# Sheet_D1.net
KiCad netlist of a schematic drawn in Altium Designer
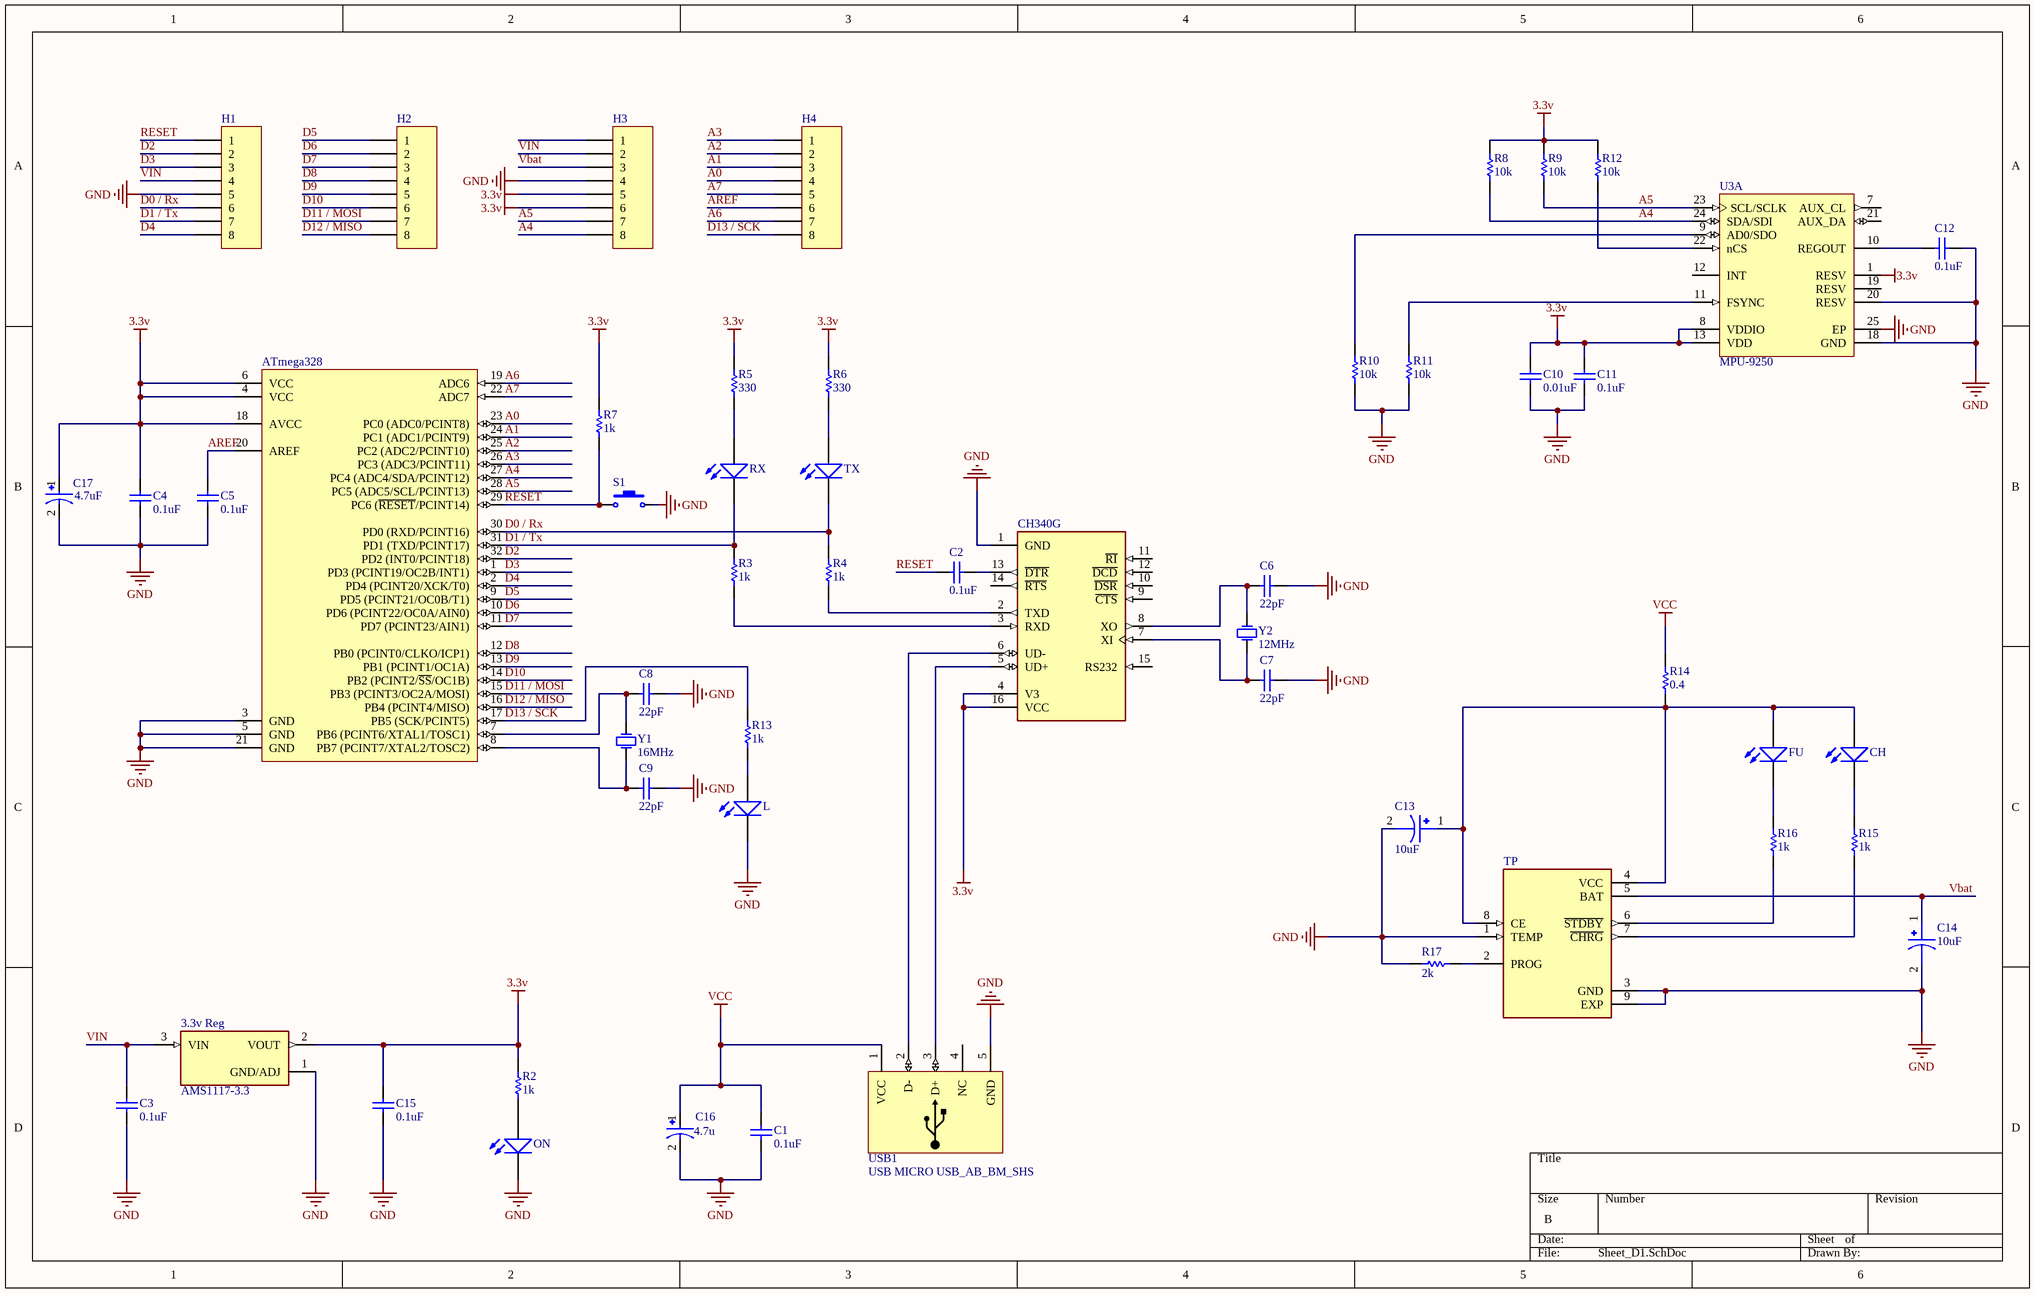
[diagram p0: Sheet_D1.SchDoc]

(export (version "E")
  (design (tool "Eeschema 10.0.6"))
  (components
    (comp (ref "3.3v Reg")
      (value "AMS1117-3.3")
      (footprint "SOT229P700X180-4N")
      (description "Sot223/Pkg 1-Amp 3.3-Volt Low Drop Out Voltage Regulatator")
      (fields (field (name "MF") "Advanced Monolithic Systems"))
      (libsource (lib "AMS1117-3.3") (part "AMS1117-3.3"))
    )
    (comp (ref "ATmega328")
      (value "~")
      (footprint "32A_L")
      (libsource (lib "Altium Content Vault") (part "MC-8B-ATM48-SQ32"))
    )
    (comp (ref "C1")
      (value "0.1uF")
      (footprint "CAP0805")
      (description "CAP0805")
      (libsource (lib "CAP0805") (part "CAP0805"))
    )
    (comp (ref "C2")
      (value "0.1uF")
      (footprint "CAP0805")
      (description "CAP0805")
      (libsource (lib "CAP0805") (part "CAP0805"))
    )
    (comp (ref "C3")
      (value "0.1uF")
      (footprint "CAP0805")
      (description "CAP0805")
      (libsource (lib "CAP0805") (part "CAP0805"))
    )
    (comp (ref "C4")
      (value "0.1uF")
      (footprint "CAP0805")
      (description "CAP0805")
      (libsource (lib "CAP0805") (part "CAP0805"))
    )
    (comp (ref "C5")
      (value "0.1uF")
      (footprint "CAP0805")
      (description "CAP0805")
      (libsource (lib "CAP0805") (part "CAP0805"))
    )
    (comp (ref "C6")
      (value "22pF")
      (footprint "CAP0805")
      (description "CAP0805")
      (libsource (lib "CAP0805") (part "CAP0805"))
    )
    (comp (ref "C7")
      (value "22pF")
      (footprint "CAP0805")
      (description "CAP0805")
      (libsource (lib "CAP0805") (part "CAP0805"))
    )
    (comp (ref "C8")
      (value "22pF")
      (footprint "CAP0805")
      (description "CAP0805")
      (libsource (lib "CAP0805") (part "CAP0805"))
    )
    (comp (ref "C9")
      (value "22pF")
      (footprint "CAP0805")
      (description "CAP0805")
      (libsource (lib "CAP0805") (part "CAP0805"))
    )
    (comp (ref "C10")
      (value "0.01uF")
      (footprint "CAP0805")
      (description "CAP0805")
      (libsource (lib "CAP0805") (part "CAP0805"))
    )
    (comp (ref "C11")
      (value "0.1uF")
      (footprint "CAP0805")
      (description "CAP0805")
      (libsource (lib "CAP0805") (part "CAP0805"))
    )
    (comp (ref "C12")
      (value "0.1uF")
      (footprint "CAP0805")
      (description "CAP0805")
      (libsource (lib "CAP0805") (part "CAP0805"))
    )
    (comp (ref "C13")
      (value "10uF")
      (footprint "CAPMP3216X180N")
      (fields (field (name "MP") "TAJA106K016RNJ") (field (name "MF") "AVX"))
      (libsource (lib "") (part "TAJA106K016RNJ_1"))
    )
    (comp (ref "C14")
      (value "10uF")
      (footprint "CAPMP3216X180N")
      (fields (field (name "MP") "TAJA106K016RNJ") (field (name "MF") "AVX"))
      (libsource (lib "TAJA106K016RNJ") (part "TAJA106K016RNJ"))
    )
    (comp (ref "C15")
      (value "0.1uF")
      (footprint "CAP0805")
      (description "CAP0805")
      (libsource (lib "CAP0805") (part "CAP0805"))
    )
    (comp (ref "C16")
      (value "4.7u")
      (footprint "CAPMP3516X190N")
      (description "4.7 ÂµF Molded Tantalum Capacitors 25 V 1411 (3528 Metric), 1210 1.5Ohm")
      (fields (field (name "MP") "TAJB475K025RNJ") (field (name "MF") "AVX"))
      (libsource (lib "TAJB475K025RNJ") (part "TAJB475K025RNJ"))
    )
    (comp (ref "C17")
      (value "4.7uF")
      (footprint "CAPMP3516X190N")
      (description "4.7 ÂµF Molded Tantalum Capacitors 25 V 1411 (3528 Metric), 1210 1.5Ohm")
      (fields (field (name "MP") "TAJB475K025RNJ") (field (name "MF") "AVX"))
      (libsource (lib "TAJB475K025RNJ") (part "TAJB475K025RNJ"))
    )
    (comp (ref "CH")
      (value "~")
      (footprint "LED_SMD_0805")
      (libsource (lib "LED_SMD_0805") (part "LED_SMD_0805"))
    )
    (comp (ref "CH340G")
      (value "~")
      (footprint "SOIC127P600X180-16N")
      (description "USB Interface Integrated Circuit")
      (fields (field (name "MP") "Ch340G") (field (name "MF") "WCH"))
      (libsource (lib "CH340G") (part "CH340G"))
    )
    (comp (ref "FU")
      (value "~")
      (footprint "LED_SMD_0805")
      (libsource (lib "LED_SMD_0805") (part "LED_SMD_0805"))
    )
    (comp (ref "H1") (value "~") (footprint "Header 8") (libsource (lib "Header 8") (part "Header 8")))
    (comp (ref "H2") (value "~") (footprint "Header 8") (libsource (lib "Header 8") (part "Header 8")))
    (comp (ref "H3") (value "~") (footprint "Header 8") (libsource (lib "Header 8") (part "Header 8")))
    (comp (ref "H4") (value "~") (footprint "Header 8") (libsource (lib "Header 8") (part "Header 8")))
    (comp (ref "L")
      (value "~")
      (footprint "LED_SMD_0805")
      (libsource (lib "LED_SMD_0805") (part "LED_SMD_0805"))
    )
    (comp (ref "ON")
      (value "~")
      (footprint "LED_SMD_0805")
      (libsource (lib "LED_SMD_0805") (part "LED_SMD_0805"))
    )
    (comp (ref "R2")
      (value "1k")
      (footprint "RES0805")
      (description "RES0805")
      (libsource (lib "RES0805") (part "RES0805"))
    )
    (comp (ref "R3")
      (value "1k")
      (footprint "RES0805")
      (description "RES0805")
      (libsource (lib "RES0805") (part "RES0805"))
    )
    (comp (ref "R4")
      (value "1k")
      (footprint "RES0805")
      (description "RES0805")
      (libsource (lib "RES0805") (part "RES0805"))
    )
    (comp (ref "R5")
      (value "330")
      (footprint "RES0805")
      (description "RES0805")
      (libsource (lib "RES0805") (part "RES0805"))
    )
    (comp (ref "R6")
      (value "330")
      (footprint "RES0805")
      (description "RES0805")
      (libsource (lib "RES0805") (part "RES0805"))
    )
    (comp (ref "R7")
      (value "1k")
      (footprint "RES0805")
      (description "RES0805")
      (libsource (lib "RES0805") (part "RES0805"))
    )
    (comp (ref "R8")
      (value "10k")
      (footprint "RES0805")
      (description "RES0805")
      (libsource (lib "RES0805") (part "RES0805"))
    )
    (comp (ref "R9")
      (value "10k")
      (footprint "RES0805")
      (description "RES0805")
      (libsource (lib "RES0805") (part "RES0805"))
    )
    (comp (ref "R10")
      (value "10k")
      (footprint "RES0805")
      (description "RES0805")
      (libsource (lib "RES0805") (part "RES0805"))
    )
    (comp (ref "R11")
      (value "10k")
      (footprint "RES0805")
      (description "RES0805")
      (libsource (lib "RES0805") (part "RES0805"))
    )
    (comp (ref "R12")
      (value "10k")
      (footprint "RES0805")
      (description "RES0805")
      (libsource (lib "RES0805") (part "RES0805"))
    )
    (comp (ref "R13")
      (value "1k")
      (footprint "RES0805")
      (description "RES0805")
      (libsource (lib "RES0805") (part "RES0805"))
    )
    (comp (ref "R14")
      (value "0.4")
      (footprint "RES0805")
      (description "RES0805")
      (libsource (lib "RES0805") (part "RES0805"))
    )
    (comp (ref "R15")
      (value "1k")
      (footprint "RES0805")
      (description "RES0805")
      (libsource (lib "RES0805") (part "RES0805"))
    )
    (comp (ref "R16")
      (value "1k")
      (footprint "RES0805")
      (description "RES0805")
      (libsource (lib "RES0805") (part "RES0805"))
    )
    (comp (ref "R17")
      (value "2k")
      (footprint "RES0805")
      (description "RES0805")
      (libsource (lib "RES0805") (part "RES0805"))
    )
    (comp (ref "RX")
      (value "~")
      (footprint "LED_SMD_0805")
      (libsource (lib "LED_SMD_0805") (part "LED_SMD_0805"))
    )
    (comp (ref "S1")
      (value "~")
      (footprint "Push Button Switch SMD")
      (libsource (lib "Push Button Switch SMD") (part "Push Button Switch SMD"))
    )
    (comp (ref "TP")
      (value "~")
      (footprint "SOIC127P600X175-9N")
      (description "TP4056-42-ESOP8 TP")
      (fields (field (name "MF") "Lite-On Semiconductor") (field (name "MP") "TP4056-42-ESOP8"))
      (libsource (lib "TP4056-42-ESOP8") (part "TP4056-42-ESOP8"))
    )
    (comp (ref "TX")
      (value "~")
      (footprint "LED_SMD_0805")
      (libsource (lib "LED_SMD_0805") (part "LED_SMD_0805"))
    )
    (comp (ref "U3")
      (value "MPU-9250")
      (footprint "INSE-QFN-24-1700X1540TP_M")
      (description "9-axis MotionTracking device, 2.4 to 3,6 V, -40 to 85 degC, 24-Pin QFN, RoHS, Tape and Reel")
      (fields (field (name "MANUFACTURER") "InvenSense"))
      (libsource (lib "Altium Content Vault") (part "INSE-MPU-9250-QFN-24"))
    )
    (comp (ref "USB1")
      (value "USB MICRO USB_AB_BM_SHS")
      (footprint "USB MICRO USB_AB_BM_SHS")
      (libsource (lib "USB MICRO USB_AB_BM_SHS") (part "USB MICRO USB_AB_BM_SHS"))
    )
    (comp (ref "Y1")
      (value "16MHz")
      (footprint "Crystal SMD")
      (description "Crystal SMD")
      (libsource (lib "Crystal SMD") (part "Crystal SMD"))
    )
    (comp (ref "Y2")
      (value "12MHz")
      (footprint "Crystal SMD")
      (description "Crystal SMD")
      (libsource (lib "Crystal SMD") (part "Crystal SMD"))
    )
  )
  (nets
    (net (code "1") (name "/A0") (class "Default")
      (node (ref "ATmega328") (pin "23") (pinfunction "PC0_(ADC0/PCINT8)_23") (pintype "bidirectional"))
      (node (ref "H4") (pin "4") (pinfunction "4_4") (pintype "passive"))
    )
    (net (code "2") (name "/A1") (class "Default")
      (node (ref "ATmega328") (pin "24") (pinfunction "PC1_(ADC1/PCINT9)_24") (pintype "bidirectional"))
      (node (ref "H4") (pin "3") (pinfunction "3_3") (pintype "passive"))
    )
    (net (code "3") (name "/A2") (class "Default")
      (node (ref "ATmega328") (pin "25") (pinfunction "PC2_(ADC2/PCINT10)_25") (pintype "bidirectional"))
      (node (ref "H4") (pin "2") (pinfunction "2_2") (pintype "passive"))
    )
    (net (code "4") (name "/A3") (class "Default")
      (node (ref "ATmega328") (pin "26") (pinfunction "PC3_(ADC3/PCINT11)_26") (pintype "bidirectional"))
      (node (ref "H4") (pin "1") (pinfunction "1_1") (pintype "passive"))
    )
    (net (code "5") (name "/A4") (class "Default")
      (node (ref "ATmega328") (pin "27") (pinfunction "PC4_(ADC4/SDA/PCINT12)_27") (pintype "bidirectional"))
      (node (ref "H3") (pin "8") (pinfunction "8_8") (pintype "passive"))
      (node (ref "R8") (pin "1") (pinfunction "1_1") (pintype "passive"))
      (node (ref "U3") (pin "24") (pinfunction "SDA/SDI_24") (pintype "bidirectional"))
    )
    (net (code "6") (name "/A5") (class "Default")
      (node (ref "ATmega328") (pin "28") (pinfunction "PC5_(ADC5/SCL/PCINT13)_28") (pintype "bidirectional"))
      (node (ref "H3") (pin "7") (pinfunction "7_7") (pintype "passive"))
      (node (ref "R9") (pin "1") (pinfunction "1_1") (pintype "passive"))
      (node (ref "U3") (pin "23") (pinfunction "SCL/SCLK_23") (pintype "input"))
    )
    (net (code "7") (name "/A6") (class "Default")
      (node (ref "ATmega328") (pin "19") (pinfunction "ADC6_19") (pintype "input"))
      (node (ref "H4") (pin "7") (pinfunction "7_7") (pintype "passive"))
    )
    (net (code "8") (name "/A7") (class "Default")
      (node (ref "ATmega328") (pin "22") (pinfunction "ADC7_22") (pintype "input"))
      (node (ref "H4") (pin "5") (pinfunction "5_5") (pintype "passive"))
    )
    (net (code "9") (name "/AREF") (class "Default")
      (node (ref "ATmega328") (pin "20") (pinfunction "AREF_20") (pintype "passive"))
      (node (ref "C5") (pin "2") (pinfunction "2_2") (pintype "passive"))
      (node (ref "H4") (pin "6") (pinfunction "6_6") (pintype "passive"))
    )
    (net (code "10") (name "/D0 {slash} Rx") (class "Default")
      (node (ref "ATmega328") (pin "30") (pinfunction "PD0_(RXD/PCINT16)_30") (pintype "bidirectional"))
      (node (ref "H1") (pin "6") (pinfunction "6_6") (pintype "passive"))
      (node (ref "R4") (pin "2") (pinfunction "2_2") (pintype "passive"))
      (node (ref "TX") (pin "1") (pinfunction "K_1") (pintype "passive"))
    )
    (net (code "11") (name "/D1 {slash} Tx") (class "Default")
      (node (ref "ATmega328") (pin "31") (pinfunction "PD1_(TXD/PCINT17)_31") (pintype "bidirectional"))
      (node (ref "H1") (pin "7") (pinfunction "7_7") (pintype "passive"))
      (node (ref "R3") (pin "2") (pinfunction "2_2") (pintype "passive"))
      (node (ref "RX") (pin "1") (pinfunction "K_1") (pintype "passive"))
    )
    (net (code "12") (name "/D2") (class "Default")
      (node (ref "ATmega328") (pin "32") (pinfunction "PD2_(INT0/PCINT18)_32") (pintype "bidirectional"))
      (node (ref "H1") (pin "2") (pinfunction "2_2") (pintype "passive"))
    )
    (net (code "13") (name "/D3") (class "Default")
      (node (ref "ATmega328") (pin "1") (pinfunction "PD3_(PCINT19/OC2B/INT1)_1") (pintype "bidirectional"))
      (node (ref "H1") (pin "3") (pinfunction "3_3") (pintype "passive"))
    )
    (net (code "14") (name "/D4") (class "Default")
      (node (ref "ATmega328") (pin "2") (pinfunction "PD4_(PCINT20/XCK/T0)_2") (pintype "bidirectional"))
      (node (ref "H1") (pin "8") (pinfunction "8_8") (pintype "passive"))
    )
    (net (code "15") (name "/D5") (class "Default")
      (node (ref "ATmega328") (pin "9") (pinfunction "PD5_(PCINT21/OC0B/T1)_9") (pintype "bidirectional"))
      (node (ref "H2") (pin "1") (pinfunction "1_1") (pintype "passive"))
    )
    (net (code "16") (name "/D6") (class "Default")
      (node (ref "ATmega328") (pin "10") (pinfunction "PD6_(PCINT22/OC0A/AIN0)_10") (pintype "bidirectional"))
      (node (ref "H2") (pin "2") (pinfunction "2_2") (pintype "passive"))
    )
    (net (code "17") (name "/D7") (class "Default")
      (node (ref "ATmega328") (pin "11") (pinfunction "PD7_(PCINT23/AIN1)_11") (pintype "bidirectional"))
      (node (ref "H2") (pin "3") (pinfunction "3_3") (pintype "passive"))
    )
    (net (code "18") (name "/D8") (class "Default")
      (node (ref "ATmega328") (pin "12") (pinfunction "PB0_(PCINT0/CLKO/ICP1)_12") (pintype "bidirectional"))
      (node (ref "H2") (pin "4") (pinfunction "4_4") (pintype "passive"))
    )
    (net (code "19") (name "/D9") (class "Default")
      (node (ref "ATmega328") (pin "13") (pinfunction "PB1_(PCINT1/OC1A)_13") (pintype "bidirectional"))
      (node (ref "H2") (pin "5") (pinfunction "5_5") (pintype "passive"))
    )
    (net (code "20") (name "/D10") (class "Default")
      (node (ref "ATmega328") (pin "14") (pinfunction "PB2_(PCINT2/~{SS}/OC1B)_14") (pintype "bidirectional"))
      (node (ref "H2") (pin "6") (pinfunction "6_6") (pintype "passive"))
    )
    (net (code "21") (name "/D11 {slash} MOSI") (class "Default")
      (node (ref "ATmega328") (pin "15") (pinfunction "PB3_(PCINT3/OC2A/MOSI)_15") (pintype "bidirectional"))
      (node (ref "H2") (pin "7") (pinfunction "7_7") (pintype "passive"))
    )
    (net (code "22") (name "/D12 {slash} MISO") (class "Default")
      (node (ref "ATmega328") (pin "16") (pinfunction "PB4_(PCINT4/MISO)_16") (pintype "bidirectional"))
      (node (ref "H2") (pin "8") (pinfunction "8_8") (pintype "passive"))
    )
    (net (code "23") (name "/D13 {slash} SCK") (class "Default")
      (node (ref "ATmega328") (pin "17") (pinfunction "PB5_(SCK/PCINT5)_17") (pintype "bidirectional"))
      (node (ref "H4") (pin "8") (pinfunction "8_8") (pintype "passive"))
      (node (ref "R13") (pin "1") (pinfunction "1_1") (pintype "passive"))
    )
    (net (code "24") (name "/RESET") (class "Default")
      (node (ref "ATmega328") (pin "29") (pinfunction "PC6_(~{RESET}/PCINT14)_29") (pintype "bidirectional"))
      (node (ref "C2") (pin "2") (pinfunction "2_2") (pintype "passive"))
      (node (ref "H1") (pin "1") (pinfunction "1_1") (pintype "passive"))
      (node (ref "R7") (pin "1") (pinfunction "1_1") (pintype "passive"))
      (node (ref "S1") (pin "1") (pinfunction "1_1") (pintype "passive"))
    )
    (net (code "25") (name "/VIN") (class "Default")
      (node (ref "3.3v Reg") (pin "3") (pinfunction "VIN_3") (pintype "input"))
      (node (ref "C3") (pin "1") (pinfunction "1_1") (pintype "passive"))
      (node (ref "H1") (pin "4") (pinfunction "4_4") (pintype "passive"))
      (node (ref "H3") (pin "2") (pinfunction "2_2") (pintype "passive"))
    )
    (net (code "26") (name "/Vbat") (class "Default")
      (node (ref "C14") (pin "1") (pinfunction "1_1") (pintype "passive"))
      (node (ref "H3") (pin "3") (pinfunction "3_3") (pintype "passive"))
      (node (ref "TP") (pin "5") (pinfunction "BAT_5") (pintype "power_in"))
    )
    (net (code "27") (name "3.3v") (class "Default")
      (node (ref "3.3v Reg") (pin "2") (pinfunction "VOUT_2") (pintype "output"))
      (node (ref "ATmega328") (pin "18") (pinfunction "AVCC_18") (pintype "power_in"))
      (node (ref "ATmega328") (pin "4") (pinfunction "VCC_4") (pintype "power_in"))
      (node (ref "ATmega328") (pin "6") (pinfunction "VCC_6") (pintype "power_in"))
      (node (ref "C10") (pin "2") (pinfunction "2_2") (pintype "passive"))
      (node (ref "C11") (pin "2") (pinfunction "2_2") (pintype "passive"))
      (node (ref "C15") (pin "2") (pinfunction "2_2") (pintype "passive"))
      (node (ref "C17") (pin "1") (pinfunction "1_1") (pintype "passive"))
      (node (ref "C4") (pin "1") (pinfunction "1_1") (pintype "passive"))
      (node (ref "CH340G") (pin "16") (pinfunction "VCC_16") (pintype "power_in"))
      (node (ref "CH340G") (pin "4") (pinfunction "V3_4") (pintype "power_in"))
      (node (ref "H3") (pin "5") (pinfunction "5_5") (pintype "passive"))
      (node (ref "H3") (pin "6") (pinfunction "6_6") (pintype "passive"))
      (node (ref "R12") (pin "2") (pinfunction "2_2") (pintype "passive"))
      (node (ref "R2") (pin "2") (pinfunction "2_2") (pintype "passive"))
      (node (ref "R5") (pin "2") (pinfunction "2_2") (pintype "passive"))
      (node (ref "R6") (pin "2") (pinfunction "2_2") (pintype "passive"))
      (node (ref "R7") (pin "2") (pinfunction "2_2") (pintype "passive"))
      (node (ref "R8") (pin "2") (pinfunction "2_2") (pintype "passive"))
      (node (ref "R9") (pin "2") (pinfunction "2_2") (pintype "passive"))
      (node (ref "U3") (pin "1") (pinfunction "RESV_1") (pintype "power_in"))
      (node (ref "U3") (pin "13") (pinfunction "VDD_13") (pintype "power_in"))
      (node (ref "U3") (pin "8") (pinfunction "VDDIO_8") (pintype "power_in"))
    )
    (net (code "28") (name "GND") (class "Default")
      (node (ref "3.3v Reg") (pin "1") (pinfunction "GND/ADJ_1") (pintype "power_in"))
      (node (ref "ATmega328") (pin "21") (pinfunction "GND_21") (pintype "power_in"))
      (node (ref "ATmega328") (pin "3") (pinfunction "GND_3") (pintype "power_in"))
      (node (ref "ATmega328") (pin "5") (pinfunction "GND_5") (pintype "power_in"))
      (node (ref "C1") (pin "1") (pinfunction "1_1") (pintype "passive"))
      (node (ref "C10") (pin "1") (pinfunction "1_1") (pintype "passive"))
      (node (ref "C11") (pin "1") (pinfunction "1_1") (pintype "passive"))
      (node (ref "C12") (pin "2") (pinfunction "2_2") (pintype "passive"))
      (node (ref "C13") (pin "2") (pinfunction "2_2") (pintype "passive"))
      (node (ref "C14") (pin "2") (pinfunction "2_2") (pintype "passive"))
      (node (ref "C15") (pin "1") (pinfunction "1_1") (pintype "passive"))
      (node (ref "C16") (pin "2") (pinfunction "2_2") (pintype "passive"))
      (node (ref "C17") (pin "2") (pinfunction "2_2") (pintype "passive"))
      (node (ref "C3") (pin "2") (pinfunction "2_2") (pintype "passive"))
      (node (ref "C4") (pin "2") (pinfunction "2_2") (pintype "passive"))
      (node (ref "C5") (pin "1") (pinfunction "1_1") (pintype "passive"))
      (node (ref "C6") (pin "1") (pinfunction "1_1") (pintype "passive"))
      (node (ref "C7") (pin "1") (pinfunction "1_1") (pintype "passive"))
      (node (ref "C8") (pin "1") (pinfunction "1_1") (pintype "passive"))
      (node (ref "C9") (pin "1") (pinfunction "1_1") (pintype "passive"))
      (node (ref "CH340G") (pin "1") (pinfunction "GND_1") (pintype "power_in"))
      (node (ref "H1") (pin "5") (pinfunction "5_5") (pintype "passive"))
      (node (ref "H3") (pin "4") (pinfunction "4_4") (pintype "passive"))
      (node (ref "L") (pin "1") (pinfunction "K_1") (pintype "passive"))
      (node (ref "ON") (pin "1") (pinfunction "K_1") (pintype "passive"))
      (node (ref "R10") (pin "2") (pinfunction "2_2") (pintype "passive"))
      (node (ref "R11") (pin "1") (pinfunction "1_1") (pintype "passive"))
      (node (ref "R17") (pin "1") (pinfunction "1_1") (pintype "passive"))
      (node (ref "S1") (pin "2") (pinfunction "2_2") (pintype "passive"))
      (node (ref "TP") (pin "1") (pinfunction "TEMP_1") (pintype "input"))
      (node (ref "TP") (pin "3") (pinfunction "GND_3") (pintype "power_in"))
      (node (ref "TP") (pin "9") (pinfunction "EXP_9") (pintype "passive"))
      (node (ref "U3") (pin "18") (pinfunction "GND_18") (pintype "power_in"))
      (node (ref "U3") (pin "20") (pinfunction "RESV_20") (pintype "power_in"))
      (node (ref "U3") (pin "25") (pinfunction "EP_25") (pintype "passive"))
      (node (ref "USB1") (pin "5") (pinfunction "GND_5") (pintype "power_in"))
    )
    (net (code "29") (name "Net-(ATmega328-PB6_(PCINT6{slash}XTAL1{slash}TOSC1))") (class "Default")
      (node (ref "ATmega328") (pin "7") (pinfunction "PB6_(PCINT6/XTAL1/TOSC1)_7") (pintype "bidirectional"))
      (node (ref "C8") (pin "2") (pinfunction "2_2") (pintype "passive"))
      (node (ref "Y1") (pin "2") (pinfunction "OSC2_2") (pintype "passive"))
    )
    (net (code "30") (name "Net-(ATmega328-PB7_(PCINT7{slash}XTAL2{slash}TOSC2))") (class "Default")
      (node (ref "ATmega328") (pin "8") (pinfunction "PB7_(PCINT7/XTAL2/TOSC2)_8") (pintype "bidirectional"))
      (node (ref "C9") (pin "2") (pinfunction "2_2") (pintype "passive"))
      (node (ref "Y1") (pin "1") (pinfunction "OSC1_1") (pintype "passive"))
    )
    (net (code "31") (name "Net-(CH-A)") (class "Default")
      (node (ref "C13") (pin "1") (pinfunction "1_1") (pintype "passive"))
      (node (ref "CH") (pin "2") (pinfunction "A_2") (pintype "passive"))
      (node (ref "FU") (pin "2") (pinfunction "A_2") (pintype "passive"))
      (node (ref "R14") (pin "1") (pinfunction "1_1") (pintype "passive"))
      (node (ref "TP") (pin "4") (pinfunction "VCC_4") (pintype "power_in"))
      (node (ref "TP") (pin "8") (pinfunction "CE_8") (pintype "input"))
    )
    (net (code "32") (name "Net-(CH-K)") (class "Default")
      (node (ref "CH") (pin "1") (pinfunction "K_1") (pintype "passive"))
      (node (ref "R15") (pin "1") (pinfunction "1_1") (pintype "passive"))
    )
    (net (code "33") (name "Net-(CH340G-RXD)") (class "Default")
      (node (ref "CH340G") (pin "3") (pinfunction "RXD_3") (pintype "input"))
      (node (ref "R3") (pin "1") (pinfunction "1_1") (pintype "passive"))
    )
    (net (code "34") (name "Net-(CH340G-TXD)") (class "Default")
      (node (ref "CH340G") (pin "2") (pinfunction "TXD_2") (pintype "output"))
      (node (ref "R4") (pin "1") (pinfunction "1_1") (pintype "passive"))
    )
    (net (code "35") (name "Net-(CH340G-UD+)") (class "Default")
      (node (ref "CH340G") (pin "5") (pinfunction "UD+_5") (pintype "bidirectional"))
      (node (ref "USB1") (pin "3") (pinfunction "D+_3") (pintype "bidirectional"))
    )
    (net (code "36") (name "Net-(CH340G-UD-)") (class "Default")
      (node (ref "CH340G") (pin "6") (pinfunction "UD-_6") (pintype "bidirectional"))
      (node (ref "USB1") (pin "2") (pinfunction "D-_2") (pintype "bidirectional"))
    )
    (net (code "37") (name "Net-(CH340G-XI)") (class "Default")
      (node (ref "C7") (pin "2") (pinfunction "2_2") (pintype "passive"))
      (node (ref "CH340G") (pin "7") (pinfunction "XI_7") (pintype "input"))
      (node (ref "Y2") (pin "1") (pinfunction "OSC1_1") (pintype "passive"))
    )
    (net (code "38") (name "Net-(CH340G-XO)") (class "Default")
      (node (ref "C6") (pin "2") (pinfunction "2_2") (pintype "passive"))
      (node (ref "CH340G") (pin "8") (pinfunction "XO_8") (pintype "output"))
      (node (ref "Y2") (pin "2") (pinfunction "OSC2_2") (pintype "passive"))
    )
    (net (code "39") (name "Net-(CH340G-~{DTR})") (class "Default")
      (node (ref "C2") (pin "1") (pinfunction "1_1") (pintype "passive"))
      (node (ref "CH340G") (pin "13") (pinfunction "~{DTR}_13") (pintype "output"))
    )
    (net (code "40") (name "Net-(FU-K)") (class "Default")
      (node (ref "FU") (pin "1") (pinfunction "K_1") (pintype "passive"))
      (node (ref "R16") (pin "2") (pinfunction "2_2") (pintype "passive"))
    )
    (net (code "41") (name "Net-(L-A)") (class "Default")
      (node (ref "L") (pin "2") (pinfunction "A_2") (pintype "passive"))
      (node (ref "R13") (pin "2") (pinfunction "2_2") (pintype "passive"))
    )
    (net (code "42") (name "Net-(ON-A)") (class "Default")
      (node (ref "ON") (pin "2") (pinfunction "A_2") (pintype "passive"))
      (node (ref "R2") (pin "1") (pinfunction "1_1") (pintype "passive"))
    )
    (net (code "43") (name "Net-(RX-A)") (class "Default")
      (node (ref "R5") (pin "1") (pinfunction "1_1") (pintype "passive"))
      (node (ref "RX") (pin "2") (pinfunction "A_2") (pintype "passive"))
    )
    (net (code "44") (name "Net-(TP-PROG)") (class "Default")
      (node (ref "R17") (pin "2") (pinfunction "2_2") (pintype "passive"))
      (node (ref "TP") (pin "2") (pinfunction "PROG_2") (pintype "passive"))
    )
    (net (code "45") (name "Net-(TP-~{CHRG})") (class "Default")
      (node (ref "R15") (pin "2") (pinfunction "2_2") (pintype "passive"))
      (node (ref "TP") (pin "7") (pinfunction "~{CHRG}_7") (pintype "output"))
    )
    (net (code "46") (name "Net-(TP-~{STDBY})") (class "Default")
      (node (ref "R16") (pin "1") (pinfunction "1_1") (pintype "passive"))
      (node (ref "TP") (pin "6") (pinfunction "~{STDBY}_6") (pintype "output"))
    )
    (net (code "47") (name "Net-(TX-A)") (class "Default")
      (node (ref "R6") (pin "1") (pinfunction "1_1") (pintype "passive"))
      (node (ref "TX") (pin "2") (pinfunction "A_2") (pintype "passive"))
    )
    (net (code "48") (name "Net-(U3A-AD0{slash}SDO)") (class "Default")
      (node (ref "R10") (pin "1") (pinfunction "1_1") (pintype "passive"))
      (node (ref "U3") (pin "9") (pinfunction "AD0/SDO_9") (pintype "bidirectional"))
    )
    (net (code "49") (name "Net-(U3A-FSYNC)") (class "Default")
      (node (ref "R11") (pin "2") (pinfunction "2_2") (pintype "passive"))
      (node (ref "U3") (pin "11") (pinfunction "FSYNC_11") (pintype "input"))
    )
    (net (code "50") (name "Net-(U3A-REGOUT)") (class "Default")
      (node (ref "C12") (pin "1") (pinfunction "1_1") (pintype "passive"))
      (node (ref "U3") (pin "10") (pinfunction "REGOUT_10") (pintype "passive"))
    )
    (net (code "51") (name "Net-(U3A-nCS)") (class "Default")
      (node (ref "R12") (pin "1") (pinfunction "1_1") (pintype "passive"))
      (node (ref "U3") (pin "22") (pinfunction "nCS_22") (pintype "input"))
    )
    (net (code "52") (name "VCC") (class "Default")
      (node (ref "C1") (pin "2") (pinfunction "2_2") (pintype "passive"))
      (node (ref "C16") (pin "1") (pinfunction "1_1") (pintype "passive"))
      (node (ref "R14") (pin "2") (pinfunction "2_2") (pintype "passive"))
      (node (ref "USB1") (pin "1") (pinfunction "VCC_1") (pintype "power_in"))
    )
    (net (code "53") (name "unconnected-(CH340G-RS232-Pad15)") (class "Default")
      (node (ref "CH340G") (pin "15") (pinfunction "RS232_15") (pintype "input"))
    )
    (net (code "54") (name "unconnected-(CH340G-~{CTS}-Pad9)") (class "Default")
      (node (ref "CH340G") (pin "9") (pinfunction "~{CTS}_9") (pintype "input"))
    )
    (net (code "55") (name "unconnected-(CH340G-~{DCD}-Pad12)") (class "Default")
      (node (ref "CH340G") (pin "12") (pinfunction "~{DCD}_12") (pintype "input"))
    )
    (net (code "56") (name "unconnected-(CH340G-~{DSR}-Pad10)") (class "Default")
      (node (ref "CH340G") (pin "10") (pinfunction "~{DSR}_10") (pintype "input"))
    )
    (net (code "57") (name "unconnected-(CH340G-~{RI}-Pad11)") (class "Default")
      (node (ref "CH340G") (pin "11") (pinfunction "~{RI}_11") (pintype "input"))
    )
    (net (code "58") (name "unconnected-(CH340G-~{RTS}-Pad14)") (class "Default")
      (node (ref "CH340G") (pin "14") (pinfunction "~{RTS}_14") (pintype "output"))
    )
    (net (code "59") (name "unconnected-(H3-Pad1)") (class "Default")
      (node (ref "H3") (pin "1") (pinfunction "1_1") (pintype "passive"))
    )
    (net (code "60") (name "unconnected-(U3A-AUX_CL-Pad7)") (class "Default")
      (node (ref "U3") (pin "7") (pinfunction "AUX_CL_7") (pintype "output"))
    )
    (net (code "61") (name "unconnected-(U3A-AUX_DA-Pad21)") (class "Default")
      (node (ref "U3") (pin "21") (pinfunction "AUX_DA_21") (pintype "bidirectional"))
    )
    (net (code "62") (name "unconnected-(U3A-INT-Pad12)") (class "Default")
      (node (ref "U3") (pin "12") (pinfunction "INT_12") (pintype "tri_state"))
    )
    (net (code "63") (name "unconnected-(U3A-RESV-Pad19)") (class "Default")
      (node (ref "U3") (pin "19") (pinfunction "RESV_19") (pintype "passive"))
    )
    (net (code "64") (name "unconnected-(USB1-NC-Pad4)") (class "Default")
      (node (ref "USB1") (pin "4") (pinfunction "NC_4") (pintype "passive"))
    )
  )
)
